# Baos_Board.net
KiCad netlist of a schematic drawn in EAGLE
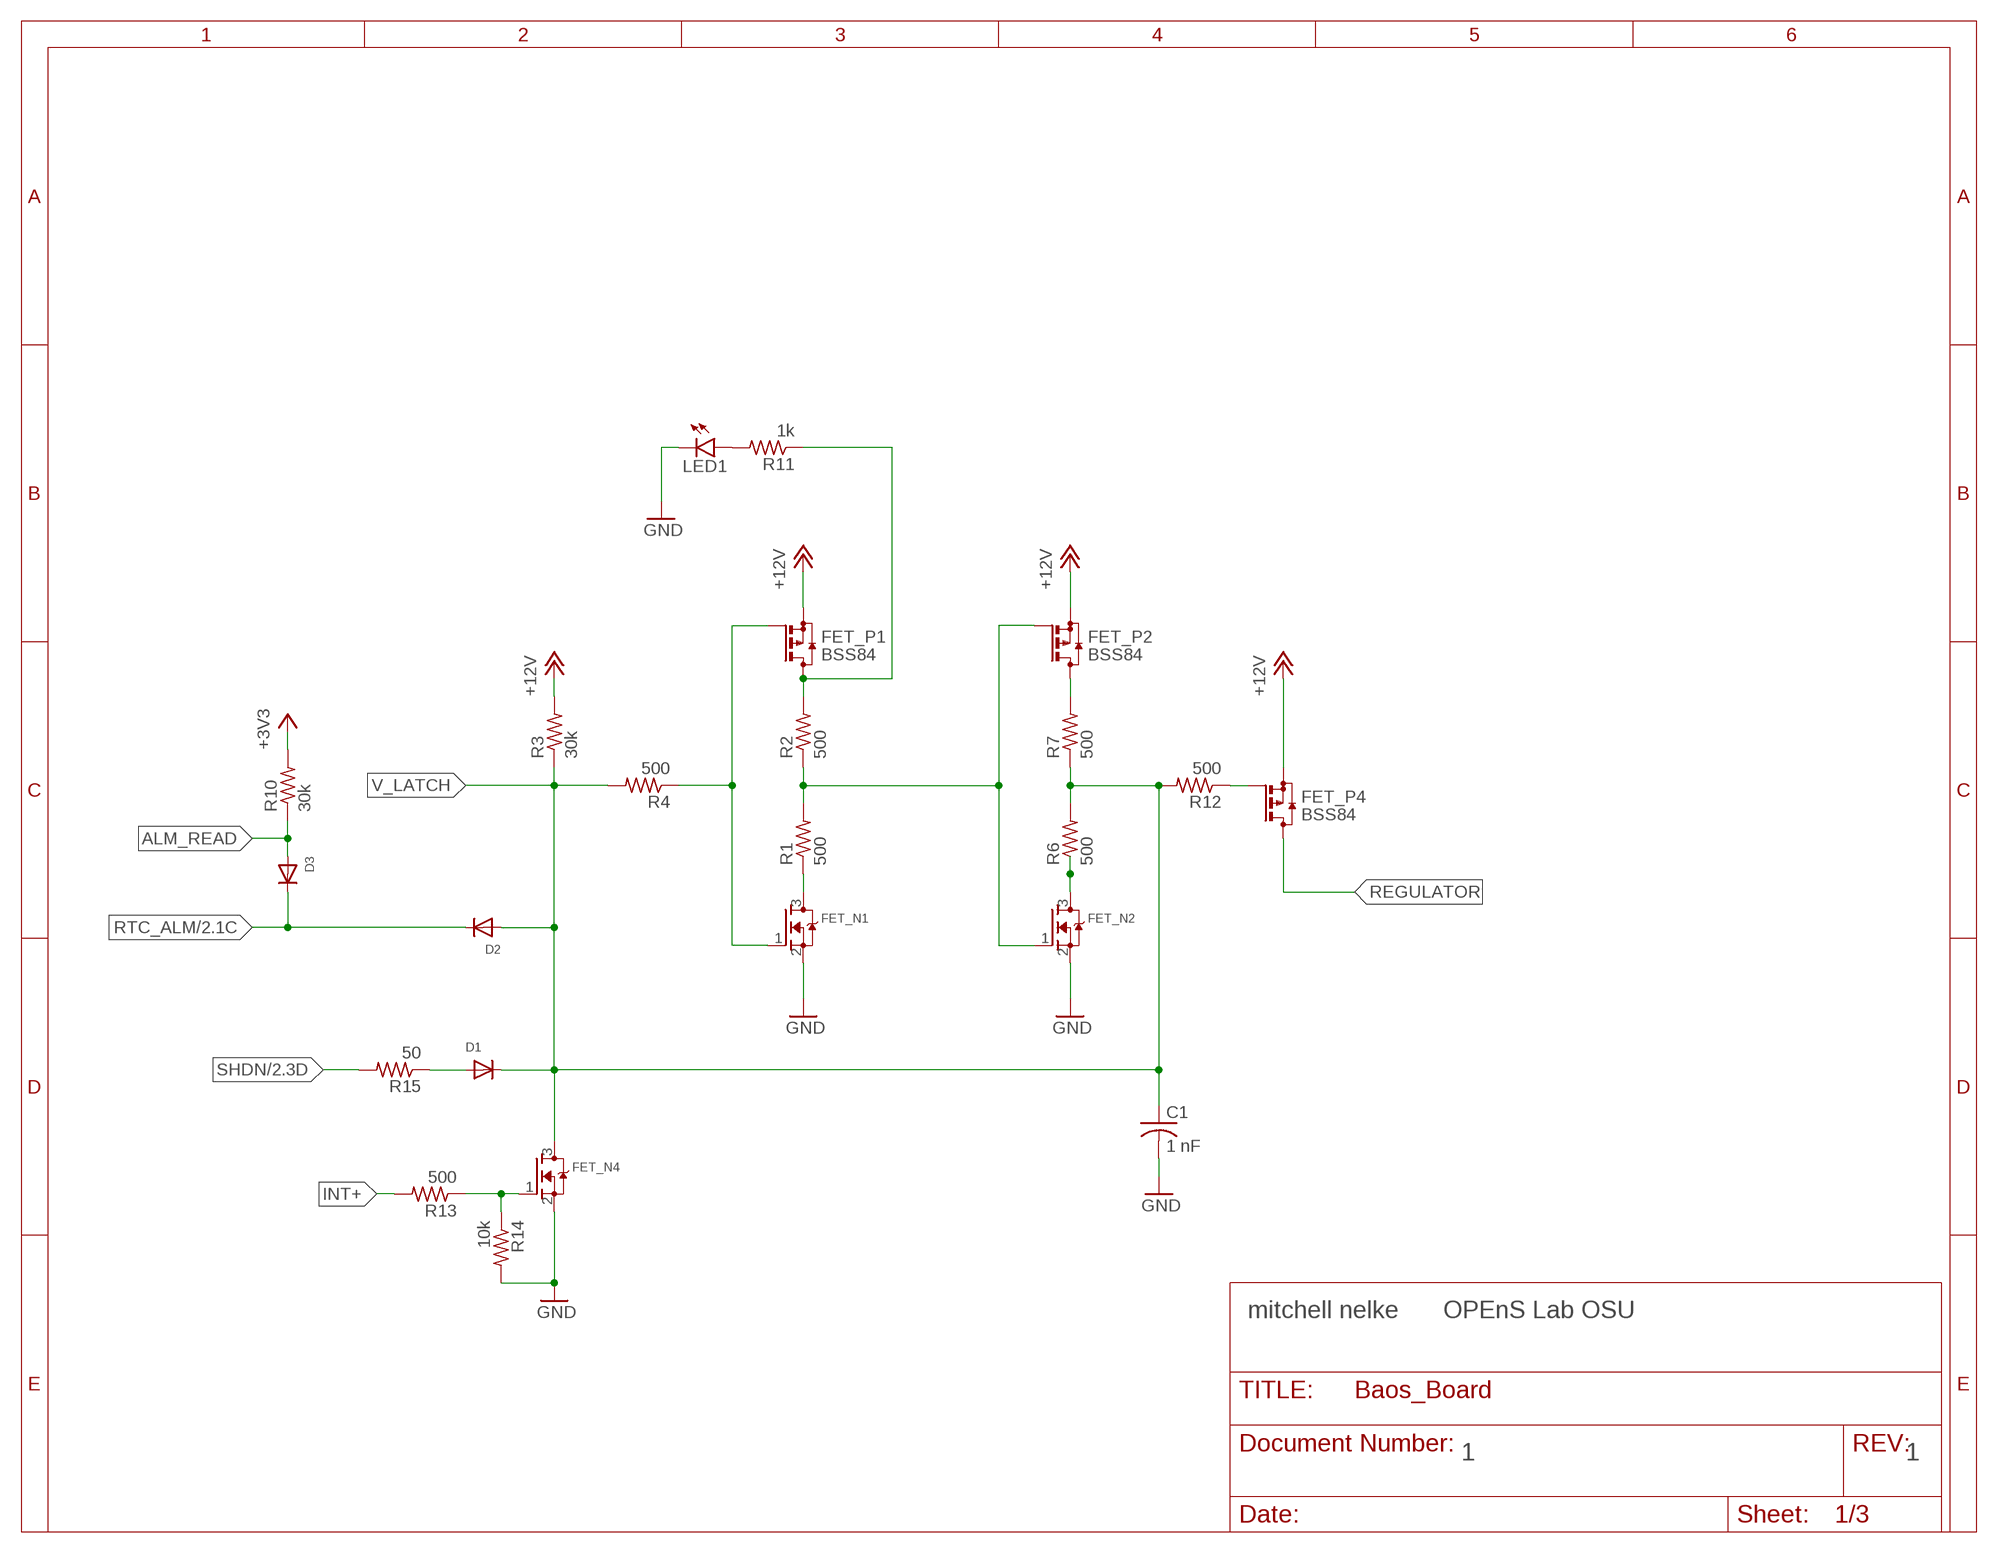
[diagram p0: schematic, sheet 1]
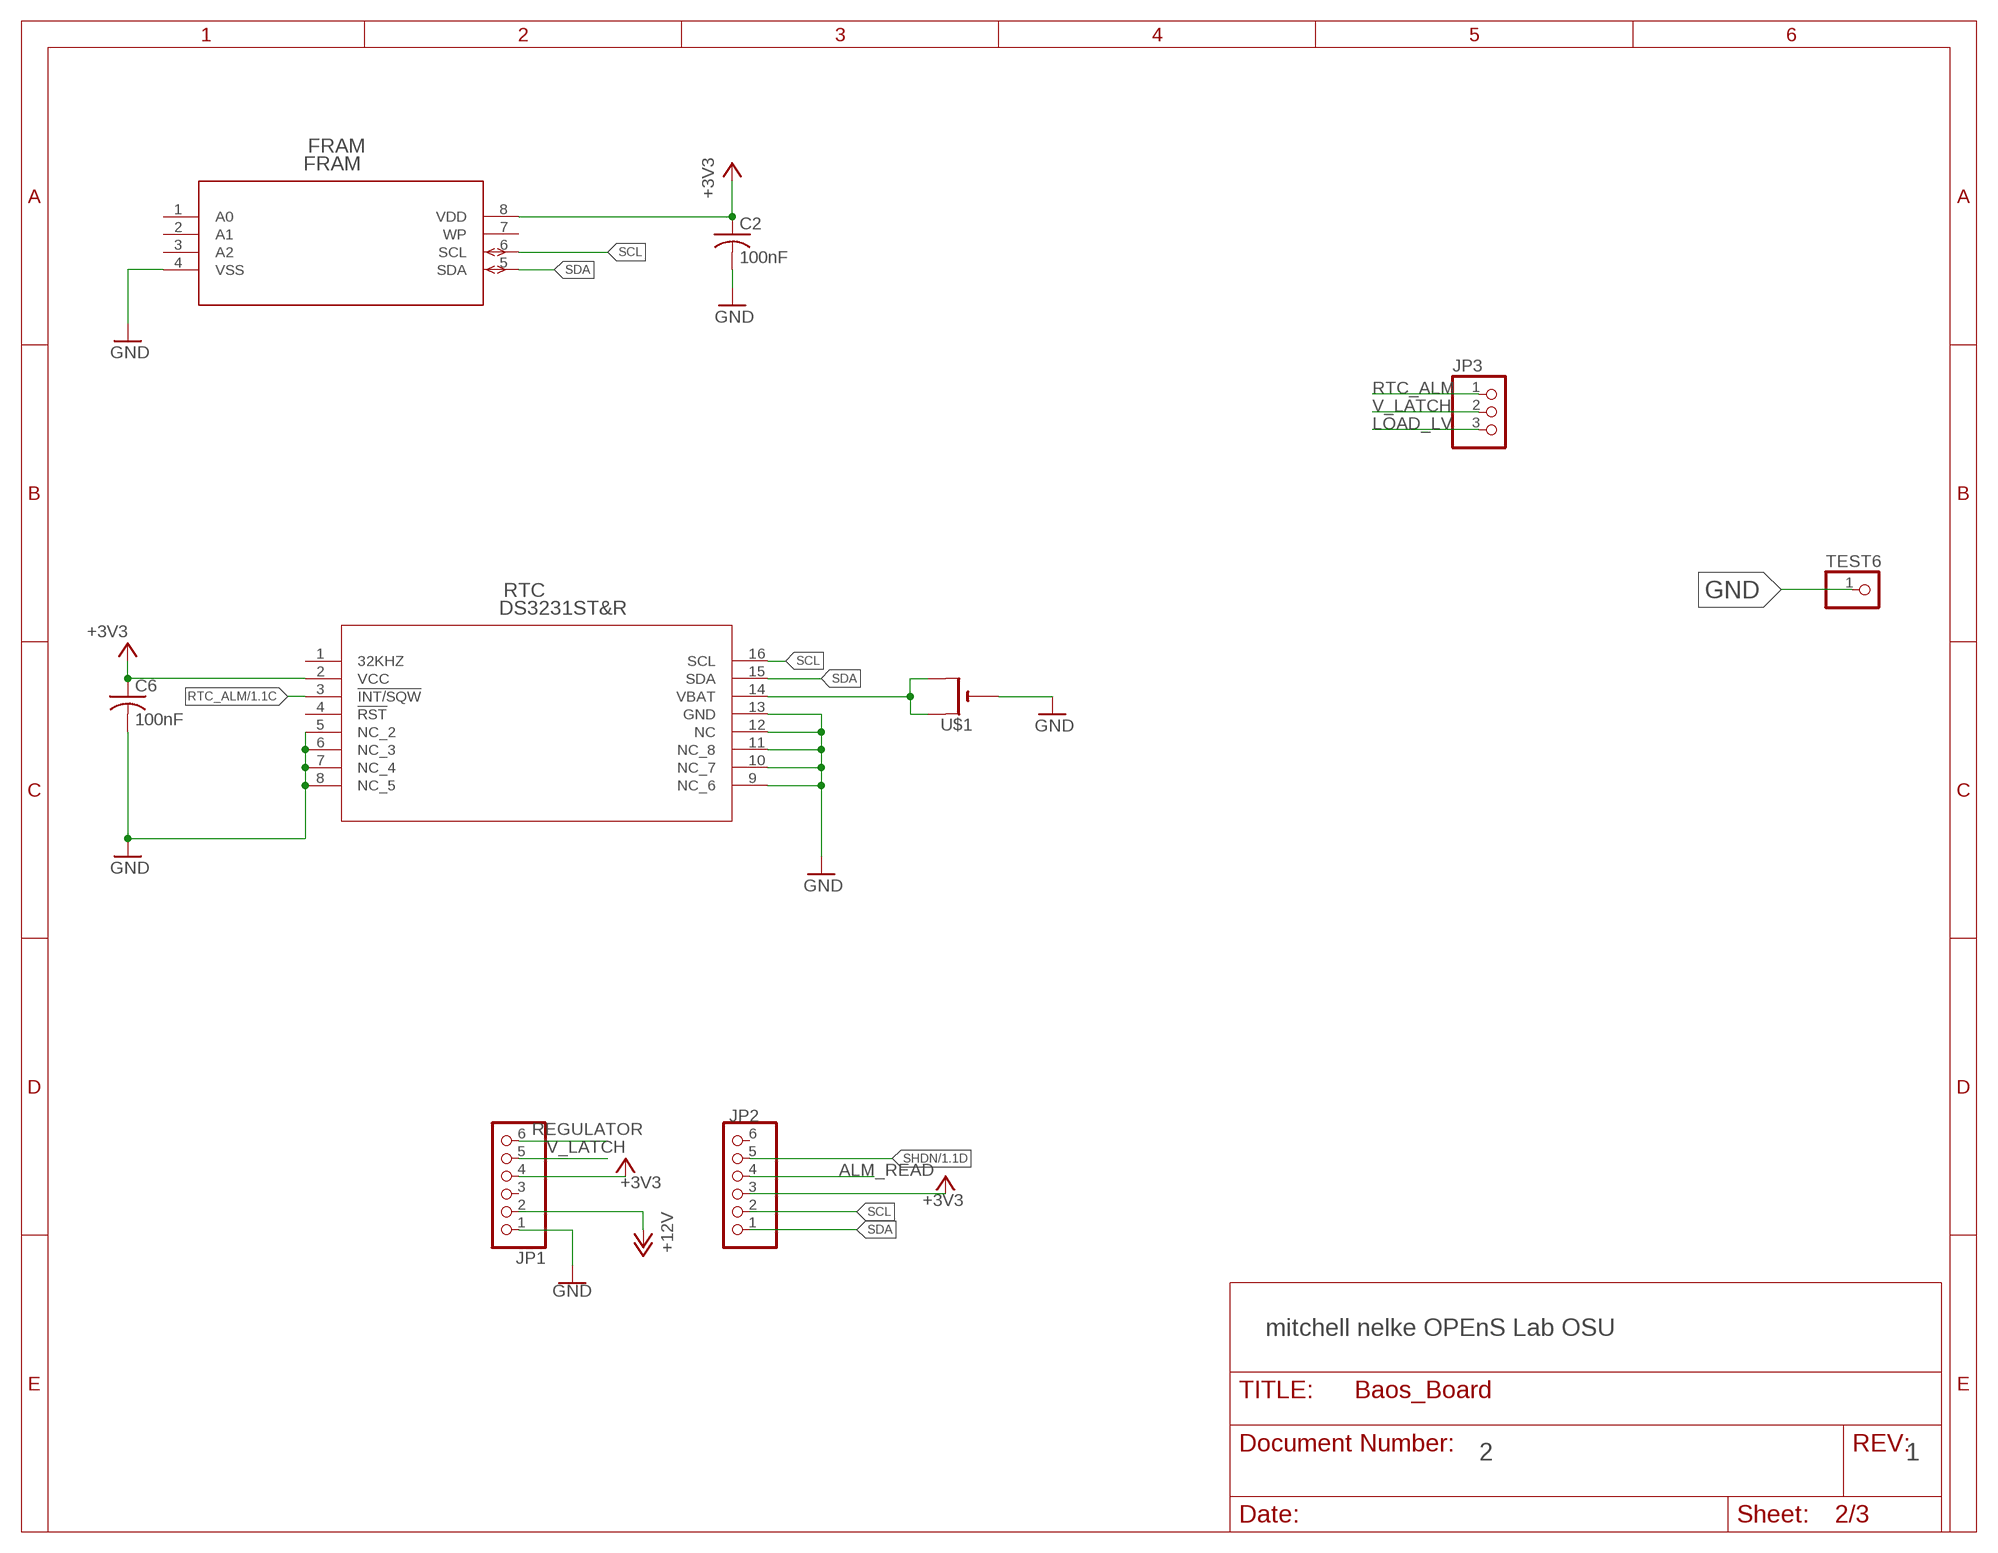
[diagram p1: schematic, sheet 2]

(export (version "E")
  (design (tool "Eeschema 10.0.6"))
  (components
    (comp (ref "C2")
      (value "100nF")
      (footprint "eagle-import:C0805")
      (libsource (lib "eagle-import") (part "C-USC0805"))
    )
    (comp (ref "C6")
      (value "100nF")
      (footprint "eagle-import:C0805")
      (libsource (lib "eagle-import") (part "C-USC0805"))
    )
    (comp (ref "FRAM")
      (value "FRAM")
      (footprint "eagle-import:FPT-8P-M02")
      (fields (field (name "MANUFACTURER_PART_NUMBER") "Inc."))
      (libsource (lib "eagle-import") (part "FRAM"))
    )
    (comp (ref "JP1")
      (value "PINHD-1X6")
      (footprint "eagle-import:1X06")
      (libsource (lib "eagle-import") (part "PINHD-1X6"))
    )
    (comp (ref "JP2")
      (value "PINHD-1X6")
      (footprint "eagle-import:1X06")
      (libsource (lib "eagle-import") (part "PINHD-1X6"))
    )
    (comp (ref "JP3")
      (value "PINHD-1X3")
      (footprint "eagle-import:1X03")
      (libsource (lib "eagle-import") (part "PINHD-1X3"))
    )
    (comp (ref "RTC")
      (value "DS3231ST&R")
      (footprint "eagle-import:21-0042B_16")
      (fields (field (name "MANUFACTURER_PART_NUMBER") "DS3231S#T&R"))
      (libsource (lib "eagle-import") (part "DS3231ST&R"))
    )
    (comp (ref "TEST6")
      (value "PINHD-1X1")
      (footprint "eagle-import:1X01")
      (libsource (lib "eagle-import") (part "PINHD-1X1"))
    )
    (comp (ref "U$1")
      (value "CR1220SMT")
      (footprint "eagle-import:CR1220-SMD")
      (libsource (lib "eagle-import") (part "CR1220SMT"))
    )
    (comp (ref "C1")
      (value "1 nF")
      (footprint "eagle-import:C0805")
      (libsource (lib "eagle-import") (part "rcl_334_C-USC0805"))
    )
    (comp (ref "D1")
      (value "DIODESOD-123")
      (footprint "eagle-import:SOD-123")
      (libsource (lib "eagle-import") (part "DIODESOD-123"))
    )
    (comp (ref "D2")
      (value "DIODESOD-123")
      (footprint "eagle-import:SOD-123")
      (libsource (lib "eagle-import") (part "DIODESOD-123"))
    )
    (comp (ref "D3")
      (value "DIODESOD-123")
      (footprint "eagle-import:SOD-123")
      (libsource (lib "eagle-import") (part "DIODESOD-123"))
    )
    (comp (ref "FET_N1")
      (value "MOSFET-NREFLOW")
      (footprint "eagle-import:SOT23")
      (libsource (lib "eagle-import") (part "MOSFET-NREFLOW"))
    )
    (comp (ref "FET_N2")
      (value "MOSFET-NREFLOW")
      (footprint "eagle-import:SOT23")
      (libsource (lib "eagle-import") (part "MOSFET-NREFLOW"))
    )
    (comp (ref "FET_N4")
      (value "MOSFET-NREFLOW")
      (footprint "eagle-import:SOT23")
      (libsource (lib "eagle-import") (part "MOSFET-NREFLOW"))
    )
    (comp (ref "FET_P1")
      (value "BSS84")
      (footprint "eagle-import:SOT23")
      (libsource (lib "eagle-import") (part "BSS84"))
    )
    (comp (ref "FET_P2")
      (value "BSS84")
      (footprint "eagle-import:SOT23")
      (libsource (lib "eagle-import") (part "BSS84"))
    )
    (comp (ref "FET_P4")
      (value "BSS84")
      (footprint "eagle-import:SOT23")
      (libsource (lib "eagle-import") (part "BSS84"))
    )
    (comp (ref "LED1")
      (value "LEDSMT1206")
      (footprint "eagle-import:1206")
      (libsource (lib "eagle-import") (part "LEDSMT1206"))
    )
    (comp (ref "R1")
      (value "500")
      (footprint "eagle-import:R0805")
      (libsource (lib "eagle-import") (part "R-US_R0805"))
    )
    (comp (ref "R2")
      (value "500")
      (footprint "eagle-import:R0805")
      (libsource (lib "eagle-import") (part "R-US_R0805"))
    )
    (comp (ref "R3")
      (value "30k")
      (footprint "eagle-import:R0805")
      (libsource (lib "eagle-import") (part "R-US_R0805"))
    )
    (comp (ref "R4")
      (value "500")
      (footprint "eagle-import:R0805")
      (libsource (lib "eagle-import") (part "R-US_R0805"))
    )
    (comp (ref "R6")
      (value "500")
      (footprint "eagle-import:R0805")
      (libsource (lib "eagle-import") (part "R-US_R0805"))
    )
    (comp (ref "R7")
      (value "500")
      (footprint "eagle-import:R0805")
      (libsource (lib "eagle-import") (part "R-US_R0805"))
    )
    (comp (ref "R10")
      (value "30k")
      (footprint "eagle-import:R0805")
      (libsource (lib "eagle-import") (part "R-US_R0805"))
    )
    (comp (ref "R11")
      (value "1k")
      (footprint "eagle-import:R0805")
      (libsource (lib "eagle-import") (part "R-US_R0805"))
    )
    (comp (ref "R12")
      (value "500")
      (footprint "eagle-import:R0805")
      (libsource (lib "eagle-import") (part "R-US_R0805"))
    )
    (comp (ref "R13")
      (value "500")
      (footprint "eagle-import:R0805")
      (libsource (lib "eagle-import") (part "R-US_R0805"))
    )
    (comp (ref "R14")
      (value "10k")
      (footprint "eagle-import:R0805")
      (libsource (lib "eagle-import") (part "R-US_R0805"))
    )
    (comp (ref "R15")
      (value "50")
      (footprint "eagle-import:R0805")
      (libsource (lib "eagle-import") (part "R-US_R0805"))
    )
  )
  (nets
    (net (code "1") (name "+3V3") (class "Default")
      (node (ref "C2") (pin "1") (pinfunction "1_1") (pintype "passive"))
      (node (ref "C6") (pin "1") (pinfunction "1_1") (pintype "passive"))
      (node (ref "FRAM") (pin "8") (pinfunction "VDD_8") (pintype "power_in"))
      (node (ref "JP1") (pin "4") (pinfunction "4_4") (pintype "passive"))
      (node (ref "JP2") (pin "3") (pinfunction "3_3") (pintype "passive"))
      (node (ref "R10") (pin "2") (pinfunction "2_2") (pintype "passive"))
      (node (ref "RTC") (pin "2") (pinfunction "VCC_2") (pintype "power_in"))
    )
    (net (code "2") (name "+12V") (class "Default")
      (node (ref "FET_P1") (pin "2") (pinfunction "S_2") (pintype "passive"))
      (node (ref "FET_P2") (pin "2") (pinfunction "S_2") (pintype "passive"))
      (node (ref "FET_P4") (pin "2") (pinfunction "S_2") (pintype "passive"))
      (node (ref "JP1") (pin "2") (pinfunction "2_2") (pintype "passive"))
      (node (ref "R3") (pin "2") (pinfunction "2_2") (pintype "passive"))
    )
    (net (code "3") (name "ALM_READ") (class "Default")
      (node (ref "D3") (pin "A") (pinfunction "A_A") (pintype "passive"))
      (node (ref "JP2") (pin "4") (pinfunction "4_4") (pintype "passive"))
      (node (ref "R10") (pin "1") (pinfunction "1_1") (pintype "passive"))
    )
    (net (code "4") (name "GND") (class "Default")
      (node (ref "C1") (pin "2") (pinfunction "2_2") (pintype "passive"))
      (node (ref "C2") (pin "2") (pinfunction "2_2") (pintype "passive"))
      (node (ref "C6") (pin "2") (pinfunction "2_2") (pintype "passive"))
      (node (ref "FET_N1") (pin "2") (pinfunction "S_2") (pintype "bidirectional"))
      (node (ref "FET_N2") (pin "2") (pinfunction "S_2") (pintype "bidirectional"))
      (node (ref "FET_N4") (pin "2") (pinfunction "S_2") (pintype "bidirectional"))
      (node (ref "FRAM") (pin "4") (pinfunction "VSS_4") (pintype "power_in"))
      (node (ref "JP1") (pin "1") (pinfunction "1_1") (pintype "passive"))
      (node (ref "LED1") (pin "C") (pinfunction "C_C") (pintype "passive"))
      (node (ref "R14") (pin "2") (pinfunction "2_2") (pintype "passive"))
      (node (ref "RTC") (pin "10") (pinfunction "NC_7_10") (pintype "passive"))
      (node (ref "RTC") (pin "11") (pinfunction "NC_8_11") (pintype "passive"))
      (node (ref "RTC") (pin "12") (pinfunction "NC_12") (pintype "passive"))
      (node (ref "RTC") (pin "13") (pinfunction "GND_13") (pintype "power_in"))
      (node (ref "RTC") (pin "5") (pinfunction "NC_2_5") (pintype "passive"))
      (node (ref "RTC") (pin "6") (pinfunction "NC_3_6") (pintype "passive"))
      (node (ref "RTC") (pin "7") (pinfunction "NC_4_7") (pintype "passive"))
      (node (ref "RTC") (pin "8") (pinfunction "NC_5_8") (pintype "passive"))
      (node (ref "RTC") (pin "9") (pinfunction "NC_6_9") (pintype "passive"))
      (node (ref "TEST6") (pin "1") (pinfunction "1_1") (pintype "passive"))
      (node (ref "U$1") (pin "-") (pinfunction "-_-") (pintype "passive"))
    )
    (net (code "5") (name "INT+") (class "Default")
      (node (ref "R13") (pin "2") (pinfunction "2_2") (pintype "passive"))
    )
    (net (code "6") (name "LOAD_LV") (class "Default")
      (node (ref "JP3") (pin "3") (pinfunction "3_3") (pintype "passive"))
    )
    (net (code "7") (name "Net-(D1-PadA)") (class "Default")
      (node (ref "D1") (pin "A") (pinfunction "A_A") (pintype "passive"))
      (node (ref "R15") (pin "1") (pinfunction "1_1") (pintype "passive"))
    )
    (net (code "8") (name "Net-(FET_N1-D)") (class "Default")
      (node (ref "FET_N1") (pin "3") (pinfunction "D_3") (pintype "bidirectional"))
      (node (ref "R1") (pin "1") (pinfunction "1_1") (pintype "passive"))
    )
    (net (code "9") (name "Net-(FET_N1-G)") (class "Default")
      (node (ref "FET_N1") (pin "1") (pinfunction "G_1") (pintype "bidirectional"))
      (node (ref "FET_P1") (pin "1") (pinfunction "G_1") (pintype "passive"))
      (node (ref "R4") (pin "1") (pinfunction "1_1") (pintype "passive"))
    )
    (net (code "10") (name "Net-(FET_N2-D)") (class "Default")
      (node (ref "FET_N2") (pin "3") (pinfunction "D_3") (pintype "bidirectional"))
      (node (ref "R6") (pin "1") (pinfunction "1_1") (pintype "passive"))
    )
    (net (code "11") (name "Net-(FET_N2-G)") (class "Default")
      (node (ref "FET_N2") (pin "1") (pinfunction "G_1") (pintype "bidirectional"))
      (node (ref "FET_P2") (pin "1") (pinfunction "G_1") (pintype "passive"))
      (node (ref "R1") (pin "2") (pinfunction "2_2") (pintype "passive"))
      (node (ref "R2") (pin "1") (pinfunction "1_1") (pintype "passive"))
    )
    (net (code "12") (name "Net-(FET_N4-G)") (class "Default")
      (node (ref "FET_N4") (pin "1") (pinfunction "G_1") (pintype "bidirectional"))
      (node (ref "R13") (pin "1") (pinfunction "1_1") (pintype "passive"))
      (node (ref "R14") (pin "1") (pinfunction "1_1") (pintype "passive"))
    )
    (net (code "13") (name "Net-(FET_P1-D)") (class "Default")
      (node (ref "FET_P1") (pin "3") (pinfunction "D_3") (pintype "passive"))
      (node (ref "R11") (pin "1") (pinfunction "1_1") (pintype "passive"))
      (node (ref "R2") (pin "2") (pinfunction "2_2") (pintype "passive"))
    )
    (net (code "14") (name "Net-(FET_P2-D)") (class "Default")
      (node (ref "FET_P2") (pin "3") (pinfunction "D_3") (pintype "passive"))
      (node (ref "R7") (pin "2") (pinfunction "2_2") (pintype "passive"))
    )
    (net (code "15") (name "Net-(FET_P4-G)") (class "Default")
      (node (ref "FET_P4") (pin "1") (pinfunction "G_1") (pintype "passive"))
      (node (ref "R12") (pin "1") (pinfunction "1_1") (pintype "passive"))
    )
    (net (code "16") (name "Net-(LED1-PadA)") (class "Default")
      (node (ref "LED1") (pin "A") (pinfunction "A_A") (pintype "passive"))
      (node (ref "R11") (pin "2") (pinfunction "2_2") (pintype "passive"))
    )
    (net (code "17") (name "Net-(RTC-VBAT)") (class "Default")
      (node (ref "RTC") (pin "14") (pinfunction "VBAT_14") (pintype "power_in"))
      (node (ref "U$1") (pin "+$1") (pinfunction "+_+$1") (pintype "passive"))
      (node (ref "U$1") (pin "+$2") (pinfunction "+1_+$2") (pintype "passive"))
    )
    (net (code "18") (name "REGULATOR") (class "Default")
      (node (ref "FET_P4") (pin "3") (pinfunction "D_3") (pintype "passive"))
      (node (ref "JP1") (pin "6") (pinfunction "6_6") (pintype "passive"))
    )
    (net (code "19") (name "RTC_ALM") (class "Default")
      (node (ref "D2") (pin "C") (pinfunction "C_C") (pintype "passive"))
      (node (ref "D3") (pin "C") (pinfunction "C_C") (pintype "passive"))
      (node (ref "JP3") (pin "1") (pinfunction "1_1") (pintype "passive"))
      (node (ref "RTC") (pin "3") (pinfunction "~{INT/SQW}_3") (pintype "passive"))
    )
    (net (code "20") (name "SCL") (class "Default")
      (node (ref "FRAM") (pin "6") (pinfunction "SCL_6") (pintype "bidirectional"))
      (node (ref "JP2") (pin "2") (pinfunction "2_2") (pintype "passive"))
      (node (ref "RTC") (pin "16") (pinfunction "SCL_16") (pintype "passive"))
    )
    (net (code "21") (name "SDA") (class "Default")
      (node (ref "FRAM") (pin "5") (pinfunction "SDA_5") (pintype "bidirectional"))
      (node (ref "JP2") (pin "1") (pinfunction "1_1") (pintype "passive"))
      (node (ref "RTC") (pin "15") (pinfunction "SDA_15") (pintype "passive"))
    )
    (net (code "22") (name "SHDN") (class "Default")
      (node (ref "JP2") (pin "5") (pinfunction "5_5") (pintype "passive"))
      (node (ref "R15") (pin "2") (pinfunction "2_2") (pintype "passive"))
    )
    (net (code "23") (name "V_LATCH") (class "Default")
      (node (ref "C1") (pin "1") (pinfunction "1_1") (pintype "passive"))
      (node (ref "D1") (pin "C") (pinfunction "C_C") (pintype "passive"))
      (node (ref "D2") (pin "A") (pinfunction "A_A") (pintype "passive"))
      (node (ref "FET_N4") (pin "3") (pinfunction "D_3") (pintype "bidirectional"))
      (node (ref "JP1") (pin "5") (pinfunction "5_5") (pintype "passive"))
      (node (ref "JP3") (pin "2") (pinfunction "2_2") (pintype "passive"))
      (node (ref "R12") (pin "2") (pinfunction "2_2") (pintype "passive"))
      (node (ref "R3") (pin "1") (pinfunction "1_1") (pintype "passive"))
      (node (ref "R4") (pin "2") (pinfunction "2_2") (pintype "passive"))
      (node (ref "R6") (pin "2") (pinfunction "2_2") (pintype "passive"))
      (node (ref "R7") (pin "1") (pinfunction "1_1") (pintype "passive"))
    )
    (net (code "24") (name "unconnected-(FRAM-A0-Pad1)") (class "Default")
      (node (ref "FRAM") (pin "1") (pinfunction "A0_1") (pintype "passive"))
    )
    (net (code "25") (name "unconnected-(FRAM-A1-Pad2)") (class "Default")
      (node (ref "FRAM") (pin "2") (pinfunction "A1_2") (pintype "passive"))
    )
    (net (code "26") (name "unconnected-(FRAM-A2-Pad3)") (class "Default")
      (node (ref "FRAM") (pin "3") (pinfunction "A2_3") (pintype "passive"))
    )
    (net (code "27") (name "unconnected-(FRAM-WP-Pad7)") (class "Default")
      (node (ref "FRAM") (pin "7") (pinfunction "WP_7") (pintype "passive"))
    )
    (net (code "28") (name "unconnected-(JP1-Pad3)") (class "Default")
      (node (ref "JP1") (pin "3") (pinfunction "3_3") (pintype "passive"))
    )
    (net (code "29") (name "unconnected-(JP2-Pad6)") (class "Default")
      (node (ref "JP2") (pin "6") (pinfunction "6_6") (pintype "passive"))
    )
    (net (code "30") (name "unconnected-(RTC-32KHZ-Pad1)") (class "Default")
      (node (ref "RTC") (pin "1") (pinfunction "32KHZ_1") (pintype "passive"))
    )
    (net (code "31") (name "unconnected-(RTC-~{RST}-Pad4)") (class "Default")
      (node (ref "RTC") (pin "4") (pinfunction "~{RST}_4") (pintype "passive"))
    )
  )
)
